# Narrow_AAA_sensor_v1.net
KiCad netlist of a schematic drawn in EAGLE
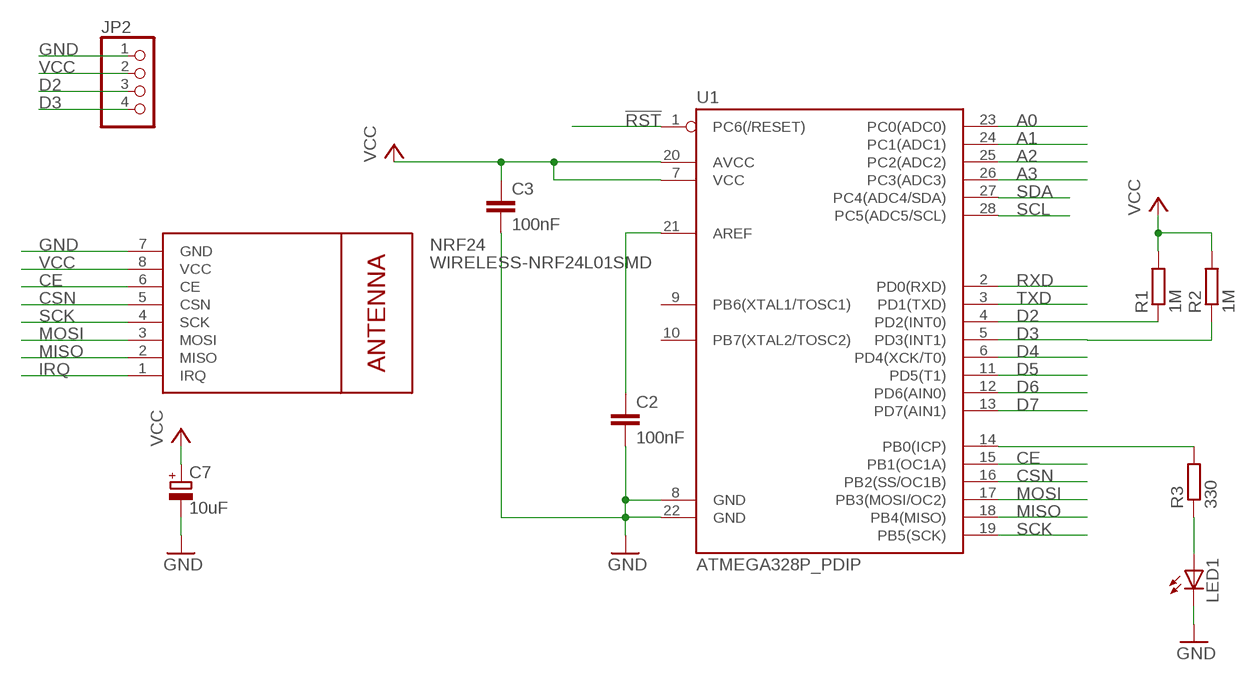
[diagram p0: schematic, sheet 1]

(export (version "E")
  (design (tool "Eeschema 10.0.6"))
  (components
    (comp (ref "C2")
      (value "100nF")
      (footprint "eagle-import:C025-025X050")
      (libsource (lib "eagle-import") (part "C-EU025-025X050"))
    )
    (comp (ref "C3")
      (value "100nF")
      (footprint "eagle-import:C025-025X050")
      (libsource (lib "eagle-import") (part "C-EU025-025X050"))
    )
    (comp (ref "C7")
      (value "10uF")
      (footprint "eagle-import:E2,5-5")
      (libsource (lib "eagle-import") (part "CPOL-EUE2.5-5"))
    )
    (comp (ref "JP2")
      (value "PINHD-1X4")
      (footprint "eagle-import:1X04")
      (libsource (lib "eagle-import") (part "PINHD-1X4"))
    )
    (comp (ref "LED1")
      (value "LED3MM")
      (footprint "eagle-import:LED3MM")
      (libsource (lib "eagle-import") (part "LED3MM"))
    )
    (comp (ref "NRF24")
      (value "WIRELESS-NRF24L01SMD")
      (footprint "eagle-import:WIRELESS-NRF24L01-SMD")
      (libsource (lib "eagle-import") (part "WIRELESS-NRF24L01SMD"))
    )
    (comp (ref "R1")
      (value "1M")
      (footprint "eagle-import:0204_7")
      (libsource (lib "eagle-import") (part "R-EU_0204/7"))
    )
    (comp (ref "R2")
      (value "1M")
      (footprint "eagle-import:0204_7")
      (libsource (lib "eagle-import") (part "R-EU_0204/7"))
    )
    (comp (ref "R3")
      (value "330")
      (footprint "eagle-import:0204_7")
      (libsource (lib "eagle-import") (part "R-EU_0204/7"))
    )
    (comp (ref "U1")
      (value "ATMEGA328P_PDIP")
      (footprint "eagle-import:DIL28-3")
      (libsource (lib "eagle-import") (part "ATMEGA328P_PDIP"))
    )
  )
  (nets
    (net (code "1") (name "/A0") (class "Default")
      (node (ref "U1") (pin "23") (pinfunction "PC0(ADC0)_23") (pintype "bidirectional"))
    )
    (net (code "2") (name "/A1") (class "Default")
      (node (ref "U1") (pin "24") (pinfunction "PC1(ADC1)_24") (pintype "bidirectional"))
    )
    (net (code "3") (name "/A2") (class "Default")
      (node (ref "U1") (pin "25") (pinfunction "PC2(ADC2)_25") (pintype "bidirectional"))
    )
    (net (code "4") (name "/A3") (class "Default")
      (node (ref "U1") (pin "26") (pinfunction "PC3(ADC3)_26") (pintype "bidirectional"))
    )
    (net (code "5") (name "/CE") (class "Default")
      (node (ref "NRF24") (pin "6") (pinfunction "CE_6") (pintype "bidirectional"))
      (node (ref "U1") (pin "15") (pinfunction "PB1(OC1A)_15") (pintype "bidirectional"))
    )
    (net (code "6") (name "/CSN") (class "Default")
      (node (ref "NRF24") (pin "5") (pinfunction "CSN_5") (pintype "bidirectional"))
      (node (ref "U1") (pin "16") (pinfunction "PB2(SS/OC1B)_16") (pintype "bidirectional"))
    )
    (net (code "7") (name "/D2") (class "Default")
      (node (ref "JP2") (pin "3") (pinfunction "3_3") (pintype "passive"))
      (node (ref "R1") (pin "1") (pinfunction "1_1") (pintype "passive"))
      (node (ref "U1") (pin "4") (pinfunction "PD2(INT0)_4") (pintype "bidirectional"))
    )
    (net (code "8") (name "/D3") (class "Default")
      (node (ref "JP2") (pin "4") (pinfunction "4_4") (pintype "passive"))
      (node (ref "R2") (pin "1") (pinfunction "1_1") (pintype "passive"))
      (node (ref "U1") (pin "5") (pinfunction "PD3(INT1)_5") (pintype "bidirectional"))
    )
    (net (code "9") (name "/D4") (class "Default")
      (node (ref "U1") (pin "6") (pinfunction "PD4(XCK/T0)_6") (pintype "bidirectional"))
    )
    (net (code "10") (name "/D5") (class "Default")
      (node (ref "U1") (pin "11") (pinfunction "PD5(T1)_11") (pintype "bidirectional"))
    )
    (net (code "11") (name "/D6") (class "Default")
      (node (ref "U1") (pin "12") (pinfunction "PD6(AIN0)_12") (pintype "bidirectional"))
    )
    (net (code "12") (name "/D7") (class "Default")
      (node (ref "U1") (pin "13") (pinfunction "PD7(AIN1)_13") (pintype "bidirectional"))
    )
    (net (code "13") (name "/IRQ") (class "Default")
      (node (ref "NRF24") (pin "1") (pinfunction "IRQ_1") (pintype "bidirectional"))
    )
    (net (code "14") (name "/MISO") (class "Default")
      (node (ref "NRF24") (pin "2") (pinfunction "MISO_2") (pintype "bidirectional"))
      (node (ref "U1") (pin "18") (pinfunction "PB4(MISO)_18") (pintype "bidirectional"))
    )
    (net (code "15") (name "/MOSI") (class "Default")
      (node (ref "NRF24") (pin "3") (pinfunction "MOSI_3") (pintype "bidirectional"))
      (node (ref "U1") (pin "17") (pinfunction "PB3(MOSI/OC2)_17") (pintype "bidirectional"))
    )
    (net (code "16") (name "/RXD") (class "Default")
      (node (ref "U1") (pin "2") (pinfunction "PD0(RXD)_2") (pintype "bidirectional"))
    )
    (net (code "17") (name "/SCK") (class "Default")
      (node (ref "NRF24") (pin "4") (pinfunction "SCK_4") (pintype "bidirectional"))
      (node (ref "U1") (pin "19") (pinfunction "PB5(SCK)_19") (pintype "bidirectional"))
    )
    (net (code "18") (name "/SCL") (class "Default")
      (node (ref "U1") (pin "28") (pinfunction "PC5(ADC5/SCL)_28") (pintype "bidirectional"))
    )
    (net (code "19") (name "/SDA") (class "Default")
      (node (ref "U1") (pin "27") (pinfunction "PC4(ADC4/SDA)_27") (pintype "bidirectional"))
    )
    (net (code "20") (name "/TXD") (class "Default")
      (node (ref "U1") (pin "3") (pinfunction "PD1(TXD)_3") (pintype "bidirectional"))
    )
    (net (code "21") (name "/~{RST}") (class "Default")
      (node (ref "U1") (pin "1") (pinfunction "PC6(/RESET)_1") (pintype "bidirectional"))
    )
    (net (code "22") (name "GND") (class "Default")
      (node (ref "C2") (pin "2") (pinfunction "2_2") (pintype "passive"))
      (node (ref "C3") (pin "2") (pinfunction "2_2") (pintype "passive"))
      (node (ref "C7") (pin "-") (pinfunction "-_-") (pintype "passive"))
      (node (ref "JP2") (pin "1") (pinfunction "1_1") (pintype "passive"))
      (node (ref "LED1") (pin "K") (pinfunction "C_K") (pintype "passive"))
      (node (ref "NRF24") (pin "7") (pinfunction "GND_7") (pintype "power_in"))
      (node (ref "U1") (pin "22") (pinfunction "GND_22") (pintype "bidirectional"))
      (node (ref "U1") (pin "8") (pinfunction "GND_8") (pintype "bidirectional"))
    )
    (net (code "23") (name "Net-(LED1-PadA)") (class "Default")
      (node (ref "LED1") (pin "A") (pinfunction "A_A") (pintype "passive"))
      (node (ref "R3") (pin "1") (pinfunction "1_1") (pintype "passive"))
    )
    (net (code "24") (name "Net-(U1-AREF)") (class "Default")
      (node (ref "C2") (pin "1") (pinfunction "1_1") (pintype "passive"))
      (node (ref "U1") (pin "21") (pinfunction "AREF_21") (pintype "bidirectional"))
    )
    (net (code "25") (name "Net-(U1-PB0(ICP))") (class "Default")
      (node (ref "R3") (pin "2") (pinfunction "2_2") (pintype "passive"))
      (node (ref "U1") (pin "14") (pinfunction "PB0(ICP)_14") (pintype "bidirectional"))
    )
    (net (code "26") (name "VCC") (class "Default")
      (node (ref "C3") (pin "1") (pinfunction "1_1") (pintype "passive"))
      (node (ref "C7") (pin "+") (pinfunction "+_+") (pintype "passive"))
      (node (ref "JP2") (pin "2") (pinfunction "2_2") (pintype "passive"))
      (node (ref "NRF24") (pin "8") (pinfunction "VCC_8") (pintype "power_in"))
      (node (ref "R1") (pin "2") (pinfunction "2_2") (pintype "passive"))
      (node (ref "R2") (pin "2") (pinfunction "2_2") (pintype "passive"))
      (node (ref "U1") (pin "20") (pinfunction "AVCC_20") (pintype "bidirectional"))
      (node (ref "U1") (pin "7") (pinfunction "VCC_7") (pintype "bidirectional"))
    )
    (net (code "27") (name "unconnected-(U1-PB6(XTAL1{slash}TOSC1)-Pad9)") (class "Default")
      (node (ref "U1") (pin "9") (pinfunction "PB6(XTAL1/TOSC1)_9") (pintype "bidirectional"))
    )
    (net (code "28") (name "unconnected-(U1-PB7(XTAL2{slash}TOSC2)-Pad10)") (class "Default")
      (node (ref "U1") (pin "10") (pinfunction "PB7(XTAL2/TOSC2)_10") (pintype "bidirectional"))
    )
  )
)
